# FrontXLRBoard.net
KiCad netlist of a schematic drawn in EAGLE
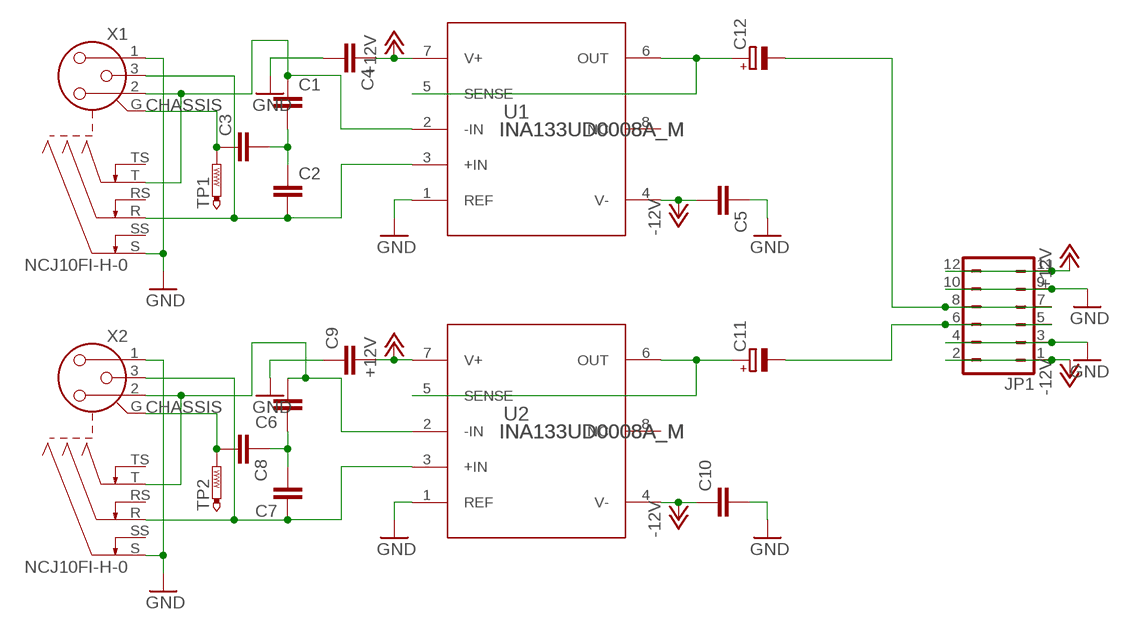
[diagram p0: schematic, sheet 1]

(export (version "E")
  (design (tool "Eeschema 10.0.6"))
  (components
    (comp (ref "C1")
      (value "C-EUC0805")
      (footprint "eagle-import:C0805")
      (libsource (lib "eagle-import") (part "C-EUC0805"))
    )
    (comp (ref "C2")
      (value "C-EUC0805")
      (footprint "eagle-import:C0805")
      (libsource (lib "eagle-import") (part "C-EUC0805"))
    )
    (comp (ref "C3")
      (value "C-EUC0805")
      (footprint "eagle-import:C0805")
      (libsource (lib "eagle-import") (part "C-EUC0805"))
    )
    (comp (ref "C4")
      (value "C-EUC0805")
      (footprint "eagle-import:C0805")
      (libsource (lib "eagle-import") (part "C-EUC0805"))
    )
    (comp (ref "C5")
      (value "C-EUC0805")
      (footprint "eagle-import:C0805")
      (libsource (lib "eagle-import") (part "C-EUC0805"))
    )
    (comp (ref "C6")
      (value "C-EUC0805")
      (footprint "eagle-import:C0805")
      (libsource (lib "eagle-import") (part "C-EUC0805"))
    )
    (comp (ref "C7")
      (value "C-EUC0805")
      (footprint "eagle-import:C0805")
      (libsource (lib "eagle-import") (part "C-EUC0805"))
    )
    (comp (ref "C8")
      (value "C-EUC0805")
      (footprint "eagle-import:C0805")
      (libsource (lib "eagle-import") (part "C-EUC0805"))
    )
    (comp (ref "C9")
      (value "C-EUC0805")
      (footprint "eagle-import:C0805")
      (libsource (lib "eagle-import") (part "C-EUC0805"))
    )
    (comp (ref "C10")
      (value "C-EUC0805")
      (footprint "eagle-import:C0805")
      (libsource (lib "eagle-import") (part "C-EUC0805"))
    )
    (comp (ref "C11")
      (value "CPOL-EU153CLV-0807")
      (footprint "eagle-import:153CLV-0807")
      (libsource (lib "eagle-import") (part "CPOL-EU153CLV-0807"))
    )
    (comp (ref "C12")
      (value "CPOL-EU153CLV-0807")
      (footprint "eagle-import:153CLV-0807")
      (libsource (lib "eagle-import") (part "CPOL-EU153CLV-0807"))
    )
    (comp (ref "JP1")
      (value "JP6Q")
      (footprint "eagle-import:JP6Q")
      (libsource (lib "eagle-import") (part "JP6Q"))
    )
    (comp (ref "TP1")
      (value "PTR1PAD1-17")
      (footprint "eagle-import:P1-17")
      (libsource (lib "eagle-import") (part "PTR1PAD1-17"))
    )
    (comp (ref "TP2")
      (value "PTR1PAD1-17")
      (footprint "eagle-import:P1-17")
      (libsource (lib "eagle-import") (part "PTR1PAD1-17"))
    )
    (comp (ref "U1")
      (value "INA133UD0008A_M")
      (footprint "eagle-import:D0008A_M")
      (fields
        (field (name "MANUFACTURER_PART_NUMBER") "INA133U")
        (field (name "COPYRIGHT") "Copyright (C) 2021 Ultra Librarian. All rights reserved.")
      )
      (libsource (lib "eagle-import") (part "INA133UD0008A_M"))
    )
    (comp (ref "U2")
      (value "INA133UD0008A_M")
      (footprint "eagle-import:D0008A_M")
      (fields
        (field (name "MANUFACTURER_PART_NUMBER") "INA133U")
        (field (name "COPYRIGHT") "Copyright (C) 2021 Ultra Librarian. All rights reserved.")
      )
      (libsource (lib "eagle-import") (part "INA133UD0008A_M"))
    )
    (comp (ref "X1")
      (value "NCJ10FI-H-0")
      (footprint "eagle-import:NCJ10FI-H-0")
      (libsource (lib "eagle-import") (part "NCJ10FI-H-0"))
    )
    (comp (ref "X2")
      (value "NCJ10FI-H-0")
      (footprint "eagle-import:NCJ10FI-H-0")
      (libsource (lib "eagle-import") (part "NCJ10FI-H-0"))
    )
  )
  (nets
    (net (code "1") (name "+12V") (class "Default")
      (node (ref "C4") (pin "1") (pinfunction "1_1") (pintype "passive"))
      (node (ref "C9") (pin "2") (pinfunction "2_2") (pintype "passive"))
      (node (ref "JP1") (pin "11") (pinfunction "11_11") (pintype "passive"))
      (node (ref "JP1") (pin "12") (pinfunction "12_12") (pintype "passive"))
      (node (ref "U1") (pin "7") (pinfunction "V+_7") (pintype "power_in"))
      (node (ref "U2") (pin "7") (pinfunction "V+_7") (pintype "power_in"))
    )
    (net (code "2") (name "-12V") (class "Default")
      (node (ref "C10") (pin "1") (pinfunction "1_1") (pintype "passive"))
      (node (ref "C5") (pin "2") (pinfunction "2_2") (pintype "passive"))
      (node (ref "JP1") (pin "1") (pinfunction "1_1") (pintype "passive"))
      (node (ref "JP1") (pin "2") (pinfunction "2_2") (pintype "passive"))
      (node (ref "U1") (pin "4") (pinfunction "V-_4") (pintype "power_in"))
      (node (ref "U2") (pin "4") (pinfunction "V-_4") (pintype "power_in"))
    )
    (net (code "3") (name "/CHASSIS") (class "Default")
      (node (ref "C3") (pin "1") (pinfunction "1_1") (pintype "passive"))
      (node (ref "C8") (pin "2") (pinfunction "2_2") (pintype "passive"))
      (node (ref "TP1") (pin "TP") (pinfunction "TP_TP") (pintype "input"))
      (node (ref "TP2") (pin "TP") (pinfunction "TP_TP") (pintype "input"))
      (node (ref "X1") (pin "G") (pinfunction "G_G") (pintype "passive"))
      (node (ref "X2") (pin "G") (pinfunction "G_G") (pintype "passive"))
    )
    (net (code "4") (name "GND") (class "Default")
      (node (ref "C10") (pin "2") (pinfunction "2_2") (pintype "passive"))
      (node (ref "C4") (pin "2") (pinfunction "2_2") (pintype "passive"))
      (node (ref "C5") (pin "1") (pinfunction "1_1") (pintype "passive"))
      (node (ref "C9") (pin "1") (pinfunction "1_1") (pintype "passive"))
      (node (ref "JP1") (pin "10") (pinfunction "10_10") (pintype "passive"))
      (node (ref "JP1") (pin "3") (pinfunction "3_3") (pintype "passive"))
      (node (ref "JP1") (pin "4") (pinfunction "4_4") (pintype "passive"))
      (node (ref "JP1") (pin "9") (pinfunction "9_9") (pintype "passive"))
      (node (ref "U1") (pin "1") (pinfunction "REF_1") (pintype "input"))
      (node (ref "U2") (pin "1") (pinfunction "REF_1") (pintype "input"))
      (node (ref "X1") (pin "1") (pinfunction "1_1") (pintype "passive"))
      (node (ref "X1") (pin "S") (pinfunction "S_S") (pintype "passive"))
      (node (ref "X2") (pin "1") (pinfunction "1_1") (pintype "passive"))
      (node (ref "X2") (pin "S") (pinfunction "S_S") (pintype "passive"))
    )
    (net (code "5") (name "Net-(C1-Pad2)") (class "Default")
      (node (ref "C1") (pin "2") (pinfunction "2_2") (pintype "passive"))
      (node (ref "C2") (pin "1") (pinfunction "1_1") (pintype "passive"))
      (node (ref "C3") (pin "2") (pinfunction "2_2") (pintype "passive"))
    )
    (net (code "6") (name "Net-(C6-Pad1)") (class "Default")
      (node (ref "C6") (pin "1") (pinfunction "1_1") (pintype "passive"))
      (node (ref "C7") (pin "2") (pinfunction "2_2") (pintype "passive"))
      (node (ref "C8") (pin "1") (pinfunction "1_1") (pintype "passive"))
    )
    (net (code "7") (name "Net-(C11-Pad-)") (class "Default")
      (node (ref "C11") (pin "-") (pinfunction "-_-") (pintype "passive"))
      (node (ref "JP1") (pin "5") (pinfunction "5_5") (pintype "passive"))
      (node (ref "JP1") (pin "6") (pinfunction "6_6") (pintype "passive"))
    )
    (net (code "8") (name "Net-(C12-Pad-)") (class "Default")
      (node (ref "C12") (pin "-") (pinfunction "-_-") (pintype "passive"))
      (node (ref "JP1") (pin "7") (pinfunction "7_7") (pintype "passive"))
      (node (ref "JP1") (pin "8") (pinfunction "8_8") (pintype "passive"))
    )
    (net (code "9") (name "Net-(U1-+IN)") (class "Default")
      (node (ref "C2") (pin "2") (pinfunction "2_2") (pintype "passive"))
      (node (ref "U1") (pin "3") (pinfunction "+IN_3") (pintype "input"))
      (node (ref "X1") (pin "3") (pinfunction "3_3") (pintype "passive"))
      (node (ref "X1") (pin "R") (pinfunction "R_R") (pintype "passive"))
    )
    (net (code "10") (name "Net-(U1--IN)") (class "Default")
      (node (ref "C1") (pin "1") (pinfunction "1_1") (pintype "passive"))
      (node (ref "U1") (pin "2") (pinfunction "-IN_2") (pintype "input"))
      (node (ref "X1") (pin "2") (pinfunction "2_2") (pintype "passive"))
      (node (ref "X1") (pin "T") (pinfunction "T_T") (pintype "passive"))
    )
    (net (code "11") (name "Net-(U1-OUT)") (class "Default")
      (node (ref "C12") (pin "+") (pinfunction "+_+") (pintype "passive"))
      (node (ref "U1") (pin "5") (pinfunction "SENSE_5") (pintype "input"))
      (node (ref "U1") (pin "6") (pinfunction "OUT_6") (pintype "output"))
    )
    (net (code "12") (name "Net-(U2-+IN)") (class "Default")
      (node (ref "C7") (pin "1") (pinfunction "1_1") (pintype "passive"))
      (node (ref "U2") (pin "3") (pinfunction "+IN_3") (pintype "input"))
      (node (ref "X2") (pin "3") (pinfunction "3_3") (pintype "passive"))
      (node (ref "X2") (pin "R") (pinfunction "R_R") (pintype "passive"))
    )
    (net (code "13") (name "Net-(U2--IN)") (class "Default")
      (node (ref "C6") (pin "2") (pinfunction "2_2") (pintype "passive"))
      (node (ref "U2") (pin "2") (pinfunction "-IN_2") (pintype "input"))
      (node (ref "X2") (pin "2") (pinfunction "2_2") (pintype "passive"))
      (node (ref "X2") (pin "T") (pinfunction "T_T") (pintype "passive"))
    )
    (net (code "14") (name "Net-(U2-OUT)") (class "Default")
      (node (ref "C11") (pin "+") (pinfunction "+_+") (pintype "passive"))
      (node (ref "U2") (pin "5") (pinfunction "SENSE_5") (pintype "input"))
      (node (ref "U2") (pin "6") (pinfunction "OUT_6") (pintype "output"))
    )
    (net (code "15") (name "unconnected-(U1-NC-Pad8)") (class "Default")
      (node (ref "U1") (pin "8") (pinfunction "NC_8") (pintype "passive"))
    )
    (net (code "16") (name "unconnected-(U2-NC-Pad8)") (class "Default")
      (node (ref "U2") (pin "8") (pinfunction "NC_8") (pintype "passive"))
    )
    (net (code "17") (name "unconnected-(X1-PadRS)") (class "Default")
      (node (ref "X1") (pin "RS") (pinfunction "RS_RS") (pintype "passive"))
    )
    (net (code "18") (name "unconnected-(X1-PadSS)") (class "Default")
      (node (ref "X1") (pin "SS") (pinfunction "SS_SS") (pintype "passive"))
    )
    (net (code "19") (name "unconnected-(X1-PadTS)") (class "Default")
      (node (ref "X1") (pin "TS") (pinfunction "TS_TS") (pintype "passive"))
    )
    (net (code "20") (name "unconnected-(X2-PadRS)") (class "Default")
      (node (ref "X2") (pin "RS") (pinfunction "RS_RS") (pintype "passive"))
    )
    (net (code "21") (name "unconnected-(X2-PadSS)") (class "Default")
      (node (ref "X2") (pin "SS") (pinfunction "SS_SS") (pintype "passive"))
    )
    (net (code "22") (name "unconnected-(X2-PadTS)") (class "Default")
      (node (ref "X2") (pin "TS") (pinfunction "TS_TS") (pintype "passive"))
    )
  )
)
